# AirPi2_Sensors.net
KiCad netlist of a schematic drawn in Altium Designer
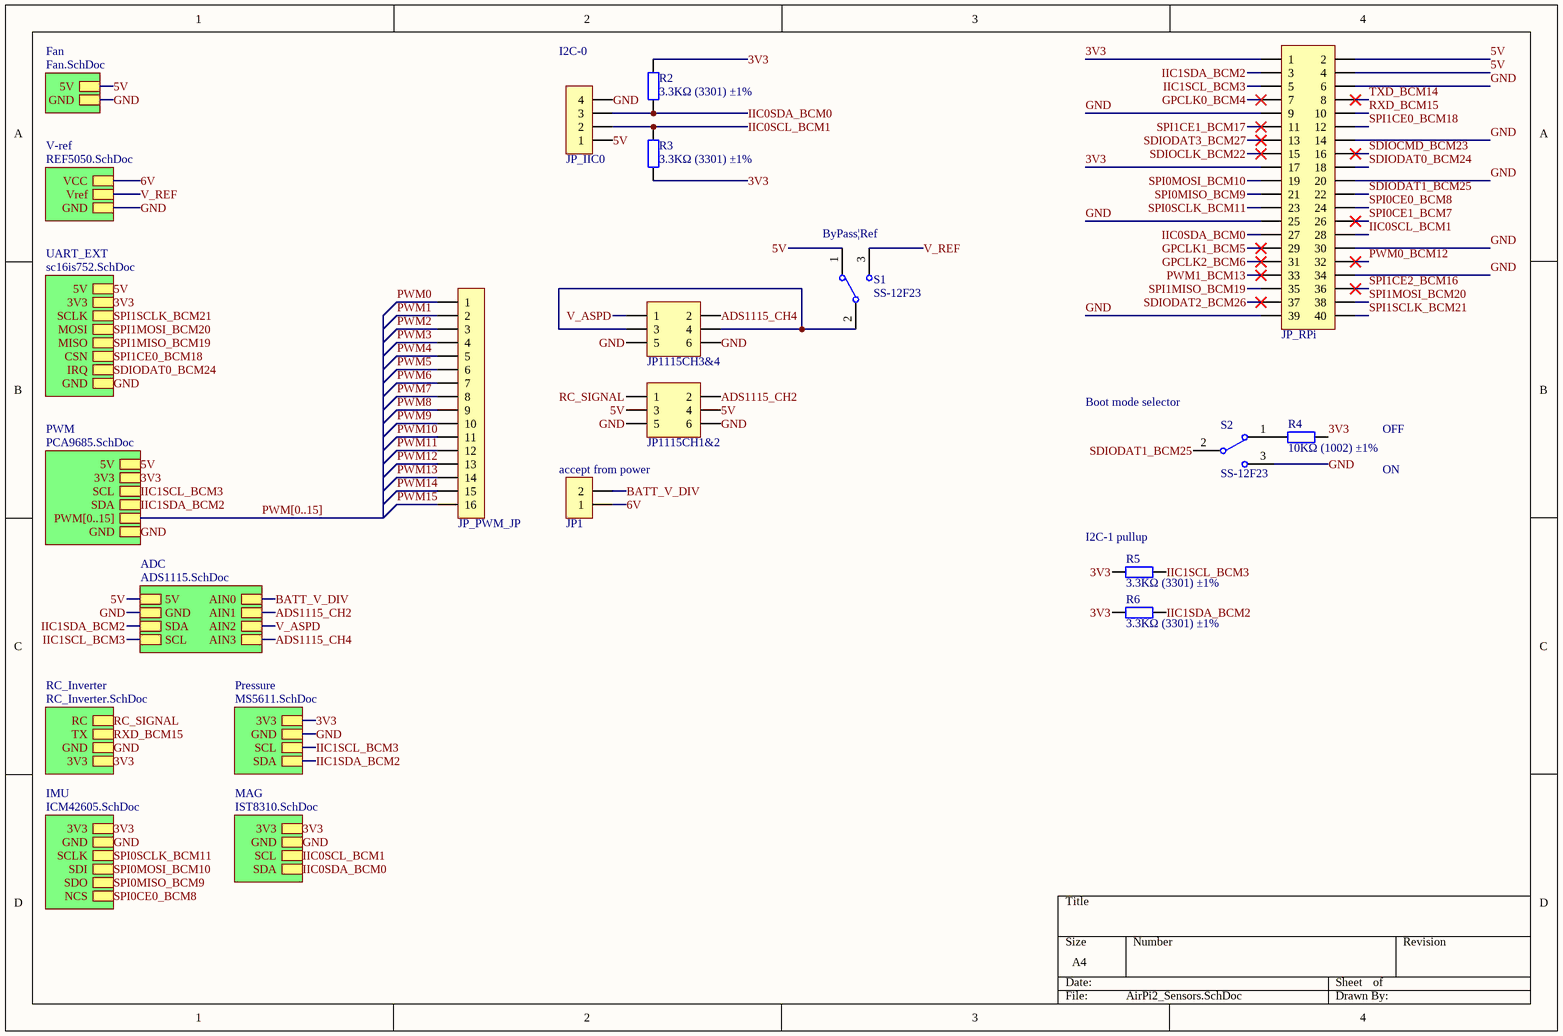
[diagram p0: AirPi2_Sensors.SchDoc]

(export (version "E")
  (design (tool "Eeschema 10.0.6"))
  (components
    (comp (ref "JP1")
      (value "HDR-1X2")
      (footprint "HDR2.54-LI-2P")
      (description "2P接插件")
      (fields (field (name "版权归属") "源创客"))
      (libsource (lib "4.5   - 接插件-脚距2.54") (part "Header 2"))
    )
    (comp (ref "JP1115CH1&2")
      (value "Header3X2")
      (footprint "HDR2.54-WI-2x3P")
      (description "3*2P接插件")
      (fields (field (name "版权归属") "源创客"))
      (libsource (lib "4.5   - 接插件-脚距2.54") (part "Header 3X2"))
    )
    (comp (ref "JP1115CH3&4")
      (value "Header3X2")
      (footprint "HDR2.54-WI-2x3P")
      (description "3*2P接插件")
      (fields (field (name "版权归属") "源创客"))
      (libsource (lib "4.5   - 接插件-脚距2.54") (part "Header 3X2"))
    )
    (comp (ref "JP_IIC0")
      (value "HDR-1X4")
      (footprint "MX 1.25-WS-4P")
      (description "4P接插件")
      (fields (field (name "版权归属") "源创客"))
      (libsource (lib "4.2   - 接插件-脚距1.25") (part "Header 4"))
    )
    (comp (ref "JP_PWM_JP")
      (value "HDR-1X16")
      (footprint "HDR2.54-LI-16P")
      (description "16P接插件")
      (fields (field (name "版权归属") "源创客"))
      (libsource (lib "4.5   - 接插件-脚距2.54") (part "Header 16"))
    )
    (comp (ref "JP_RPi")
      (value "Header 2X11")
      (footprint "HDR2.54-LI-2x20P")
      (description "20*2P接插件")
      (fields (field (name "版权归属") "源创客"))
      (libsource (lib "4.5   - 接插件-脚距2.54") (part "Header 20X2"))
    )
    (comp (ref "R2")
      (value "3.3KΩ (3301) ±1%")
      (footprint "0402_R")
      (description "贴片电阻")
      (libsource (lib "") (part "0402 3.3KΩ (3301) 1%_1"))
    )
    (comp (ref "R3")
      (value "3.3KΩ (3301) ±1%")
      (footprint "0402_R")
      (description "贴片电阻")
      (libsource (lib "") (part "0402 3.3KΩ (3301) 1%_1"))
    )
    (comp (ref "R4")
      (value "10KΩ (1002) ±1%")
      (footprint "0402_R")
      (description "贴片电阻")
      (libsource (lib "Miscellaneous Devices LC") (part "0402 10KΩ (1002) 1%"))
    )
    (comp (ref "R5")
      (value "3.3KΩ (3301) ±1%")
      (footprint "0402_R")
      (description "贴片电阻")
      (libsource (lib "Miscellaneous Devices LC") (part "0402 3.3KΩ (3301) 1%"))
    )
    (comp (ref "R6")
      (value "3.3KΩ (3301) ±1%")
      (footprint "0402_R")
      (description "贴片电阻")
      (libsource (lib "Miscellaneous Devices LC") (part "0402 3.3KΩ (3301) 1%"))
    )
    (comp (ref "S1")
      (value "SS-12F23")
      (footprint "MSK-12C01-07")
      (description "1路波动开关")
      (fields (field (name "版权归属") "源创客"))
      (libsource (lib "5.1   - 按键-开关") (part "SSW-1P"))
    )
    (comp (ref "S2")
      (value "SS-12F23")
      (footprint "MSK-12C01-07")
      (description "1路波动开关")
      (fields (field (name "版权归属") "源创客"))
      (libsource (lib "5.1   - 按键-开关") (part "SSW-1P"))
    )
  )
  (nets
    (net (code "1") (name "/3V3") (class "Default")
      (node (ref "JP_RPi") (pin "1") (pinfunction "1_1") (pintype "passive"))
      (node (ref "JP_RPi") (pin "17") (pinfunction "17_17") (pintype "passive"))
      (node (ref "R2") (pin "2") (pinfunction "2_2") (pintype "passive"))
      (node (ref "R3") (pin "1") (pinfunction "1_1") (pintype "passive"))
      (node (ref "R4") (pin "2") (pinfunction "2_2") (pintype "passive"))
      (node (ref "R5") (pin "1") (pinfunction "1_1") (pintype "passive"))
      (node (ref "R6") (pin "1") (pinfunction "1_1") (pintype "passive"))
    )
    (net (code "2") (name "/5V") (class "Default")
      (node (ref "JP1115CH1&2") (pin "3") (pinfunction "3_3") (pintype "passive"))
      (node (ref "JP1115CH1&2") (pin "4") (pinfunction "4_4") (pintype "passive"))
      (node (ref "JP_IIC0") (pin "1") (pinfunction "1_1") (pintype "passive"))
      (node (ref "JP_RPi") (pin "2") (pinfunction "2_2") (pintype "passive"))
      (node (ref "JP_RPi") (pin "4") (pinfunction "4_4") (pintype "passive"))
      (node (ref "S1") (pin "1") (pinfunction "1_1") (pintype "passive"))
    )
    (net (code "3") (name "/6V") (class "Default")
      (node (ref "JP1") (pin "1") (pinfunction "1_1") (pintype "passive"))
    )
    (net (code "4") (name "/ADS1115_CH2") (class "Default")
      (node (ref "JP1115CH1&2") (pin "2") (pinfunction "2_2") (pintype "passive"))
    )
    (net (code "5") (name "/ADS1115_CH4") (class "Default")
      (node (ref "JP1115CH3&4") (pin "2") (pinfunction "2_2") (pintype "passive"))
    )
    (net (code "6") (name "/BATT_V_DIV") (class "Default")
      (node (ref "JP1") (pin "2") (pinfunction "2_2") (pintype "passive"))
    )
    (net (code "7") (name "/GND") (class "Default")
      (node (ref "JP1115CH1&2") (pin "5") (pinfunction "5_5") (pintype "passive"))
      (node (ref "JP1115CH1&2") (pin "6") (pinfunction "6_6") (pintype "passive"))
      (node (ref "JP1115CH3&4") (pin "5") (pinfunction "5_5") (pintype "passive"))
      (node (ref "JP1115CH3&4") (pin "6") (pinfunction "6_6") (pintype "passive"))
      (node (ref "JP_IIC0") (pin "4") (pinfunction "4_4") (pintype "passive"))
      (node (ref "JP_RPi") (pin "14") (pinfunction "14_14") (pintype "passive"))
      (node (ref "JP_RPi") (pin "20") (pinfunction "20_20") (pintype "passive"))
      (node (ref "JP_RPi") (pin "25") (pinfunction "25_25") (pintype "passive"))
      (node (ref "JP_RPi") (pin "30") (pinfunction "30_30") (pintype "passive"))
      (node (ref "JP_RPi") (pin "34") (pinfunction "34_34") (pintype "passive"))
      (node (ref "JP_RPi") (pin "39") (pinfunction "39_39") (pintype "passive"))
      (node (ref "JP_RPi") (pin "6") (pinfunction "6_6") (pintype "passive"))
      (node (ref "JP_RPi") (pin "9") (pinfunction "9_9") (pintype "passive"))
      (node (ref "S2") (pin "3") (pinfunction "3_3") (pintype "passive"))
    )
    (net (code "8") (name "/GPCLK0_BCM4") (class "Default")
      (node (ref "JP_RPi") (pin "7") (pinfunction "7_7") (pintype "passive+no_connect"))
    )
    (net (code "9") (name "/GPCLK1_BCM5") (class "Default")
      (node (ref "JP_RPi") (pin "29") (pinfunction "29_29") (pintype "passive+no_connect"))
    )
    (net (code "10") (name "/GPCLK2_BCM6") (class "Default")
      (node (ref "JP_RPi") (pin "31") (pinfunction "31_31") (pintype "passive+no_connect"))
    )
    (net (code "11") (name "/IIC0SCL_BCM1") (class "Default")
      (node (ref "JP_IIC0") (pin "2") (pinfunction "2_2") (pintype "passive"))
      (node (ref "JP_RPi") (pin "28") (pinfunction "28_28") (pintype "passive"))
      (node (ref "R3") (pin "2") (pinfunction "2_2") (pintype "passive"))
    )
    (net (code "12") (name "/IIC0SDA_BCM0") (class "Default")
      (node (ref "JP_IIC0") (pin "3") (pinfunction "3_3") (pintype "passive"))
      (node (ref "JP_RPi") (pin "27") (pinfunction "27_27") (pintype "passive"))
      (node (ref "R2") (pin "1") (pinfunction "1_1") (pintype "passive"))
    )
    (net (code "13") (name "/IIC1SCL_BCM3") (class "Default")
      (node (ref "JP_RPi") (pin "5") (pinfunction "5_5") (pintype "passive"))
      (node (ref "R5") (pin "2") (pinfunction "2_2") (pintype "passive"))
    )
    (net (code "14") (name "/IIC1SDA_BCM2") (class "Default")
      (node (ref "JP_RPi") (pin "3") (pinfunction "3_3") (pintype "passive"))
      (node (ref "R6") (pin "2") (pinfunction "2_2") (pintype "passive"))
    )
    (net (code "15") (name "/PWM0") (class "Default")
      (node (ref "JP_PWM_JP") (pin "1") (pinfunction "1_1") (pintype "passive"))
    )
    (net (code "16") (name "/PWM0_BCM12") (class "Default")
      (node (ref "JP_RPi") (pin "32") (pinfunction "32_32") (pintype "passive+no_connect"))
    )
    (net (code "17") (name "/PWM1") (class "Default")
      (node (ref "JP_PWM_JP") (pin "2") (pinfunction "2_2") (pintype "passive"))
    )
    (net (code "18") (name "/PWM1_BCM13") (class "Default")
      (node (ref "JP_RPi") (pin "33") (pinfunction "33_33") (pintype "passive+no_connect"))
    )
    (net (code "19") (name "/PWM2") (class "Default")
      (node (ref "JP_PWM_JP") (pin "3") (pinfunction "3_3") (pintype "passive"))
    )
    (net (code "20") (name "/PWM3") (class "Default")
      (node (ref "JP_PWM_JP") (pin "4") (pinfunction "4_4") (pintype "passive"))
    )
    (net (code "21") (name "/PWM4") (class "Default")
      (node (ref "JP_PWM_JP") (pin "5") (pinfunction "5_5") (pintype "passive"))
    )
    (net (code "22") (name "/PWM5") (class "Default")
      (node (ref "JP_PWM_JP") (pin "6") (pinfunction "6_6") (pintype "passive"))
    )
    (net (code "23") (name "/PWM6") (class "Default")
      (node (ref "JP_PWM_JP") (pin "7") (pinfunction "7_7") (pintype "passive"))
    )
    (net (code "24") (name "/PWM7") (class "Default")
      (node (ref "JP_PWM_JP") (pin "8") (pinfunction "8_8") (pintype "passive"))
    )
    (net (code "25") (name "/PWM8") (class "Default")
      (node (ref "JP_PWM_JP") (pin "9") (pinfunction "9_9") (pintype "passive"))
    )
    (net (code "26") (name "/PWM9") (class "Default")
      (node (ref "JP_PWM_JP") (pin "10") (pinfunction "10_10") (pintype "passive"))
    )
    (net (code "27") (name "/PWM10") (class "Default")
      (node (ref "JP_PWM_JP") (pin "11") (pinfunction "11_11") (pintype "passive"))
    )
    (net (code "28") (name "/PWM11") (class "Default")
      (node (ref "JP_PWM_JP") (pin "12") (pinfunction "12_12") (pintype "passive"))
    )
    (net (code "29") (name "/PWM12") (class "Default")
      (node (ref "JP_PWM_JP") (pin "13") (pinfunction "13_13") (pintype "passive"))
    )
    (net (code "30") (name "/PWM13") (class "Default")
      (node (ref "JP_PWM_JP") (pin "14") (pinfunction "14_14") (pintype "passive"))
    )
    (net (code "31") (name "/PWM14") (class "Default")
      (node (ref "JP_PWM_JP") (pin "15") (pinfunction "15_15") (pintype "passive"))
    )
    (net (code "32") (name "/PWM15") (class "Default")
      (node (ref "JP_PWM_JP") (pin "16") (pinfunction "16_16") (pintype "passive"))
    )
    (net (code "34") (name "/RC_SIGNAL") (class "Default")
      (node (ref "JP1115CH1&2") (pin "1") (pinfunction "1_1") (pintype "passive"))
    )
    (net (code "35") (name "/RXD_BCM15") (class "Default")
      (node (ref "JP_RPi") (pin "10") (pinfunction "10_10") (pintype "passive"))
    )
    (net (code "36") (name "/SDIOCLK_BCM22") (class "Default")
      (node (ref "JP_RPi") (pin "15") (pinfunction "15_15") (pintype "passive+no_connect"))
    )
    (net (code "37") (name "/SDIOCMD_BCM23") (class "Default")
      (node (ref "JP_RPi") (pin "16") (pinfunction "16_16") (pintype "passive+no_connect"))
    )
    (net (code "38") (name "/SDIODAT0_BCM24") (class "Default")
      (node (ref "JP_RPi") (pin "18") (pinfunction "18_18") (pintype "passive"))
    )
    (net (code "39") (name "/SDIODAT1_BCM25") (class "Default")
      (node (ref "JP_RPi") (pin "22") (pinfunction "22_22") (pintype "passive"))
      (node (ref "S2") (pin "2") (pinfunction "2_2") (pintype "passive"))
    )
    (net (code "40") (name "/SDIODAT2_BCM26") (class "Default")
      (node (ref "JP_RPi") (pin "37") (pinfunction "37_37") (pintype "passive+no_connect"))
    )
    (net (code "41") (name "/SDIODAT3_BCM27") (class "Default")
      (node (ref "JP_RPi") (pin "13") (pinfunction "13_13") (pintype "passive+no_connect"))
    )
    (net (code "42") (name "/SPI0CE0_BCM8") (class "Default")
      (node (ref "JP_RPi") (pin "24") (pinfunction "24_24") (pintype "passive"))
    )
    (net (code "43") (name "/SPI0CE1_BCM7") (class "Default")
      (node (ref "JP_RPi") (pin "26") (pinfunction "26_26") (pintype "passive+no_connect"))
    )
    (net (code "44") (name "/SPI0MISO_BCM9") (class "Default")
      (node (ref "JP_RPi") (pin "21") (pinfunction "21_21") (pintype "passive"))
    )
    (net (code "45") (name "/SPI0MOSI_BCM10") (class "Default")
      (node (ref "JP_RPi") (pin "19") (pinfunction "19_19") (pintype "passive"))
    )
    (net (code "46") (name "/SPI0SCLK_BCM11") (class "Default")
      (node (ref "JP_RPi") (pin "23") (pinfunction "23_23") (pintype "passive"))
    )
    (net (code "47") (name "/SPI1CE0_BCM18") (class "Default")
      (node (ref "JP_RPi") (pin "12") (pinfunction "12_12") (pintype "passive"))
    )
    (net (code "48") (name "/SPI1CE1_BCM17") (class "Default")
      (node (ref "JP_RPi") (pin "11") (pinfunction "11_11") (pintype "passive+no_connect"))
    )
    (net (code "49") (name "/SPI1CE2_BCM16") (class "Default")
      (node (ref "JP_RPi") (pin "36") (pinfunction "36_36") (pintype "passive+no_connect"))
    )
    (net (code "50") (name "/SPI1MISO_BCM19") (class "Default")
      (node (ref "JP_RPi") (pin "35") (pinfunction "35_35") (pintype "passive"))
    )
    (net (code "51") (name "/SPI1MOSI_BCM20") (class "Default")
      (node (ref "JP_RPi") (pin "38") (pinfunction "38_38") (pintype "passive"))
    )
    (net (code "52") (name "/SPI1SCLK_BCM21") (class "Default")
      (node (ref "JP_RPi") (pin "40") (pinfunction "40_40") (pintype "passive"))
    )
    (net (code "53") (name "/TXD_BCM14") (class "Default")
      (node (ref "JP_RPi") (pin "8") (pinfunction "8_8") (pintype "passive+no_connect"))
    )
    (net (code "54") (name "/V_ASPD") (class "Default")
      (node (ref "JP1115CH3&4") (pin "1") (pinfunction "1_1") (pintype "passive"))
    )
    (net (code "55") (name "/V_REF") (class "Default")
      (node (ref "S1") (pin "3") (pinfunction "3_3") (pintype "passive"))
    )
    (net (code "56") (name "Net-(JP1115CH3&4-Pad3)") (class "Default")
      (node (ref "JP1115CH3&4") (pin "3") (pinfunction "3_3") (pintype "passive"))
      (node (ref "JP1115CH3&4") (pin "4") (pinfunction "4_4") (pintype "passive"))
      (node (ref "S1") (pin "2") (pinfunction "2_2") (pintype "passive"))
    )
    (net (code "57") (name "Net-(R4-Pad1)") (class "Default")
      (node (ref "R4") (pin "1") (pinfunction "1_1") (pintype "passive"))
      (node (ref "S2") (pin "1") (pinfunction "1_1") (pintype "passive"))
    )
  )
)
